# LM1117SW.net
KiCad netlist of a schematic drawn in EAGLE
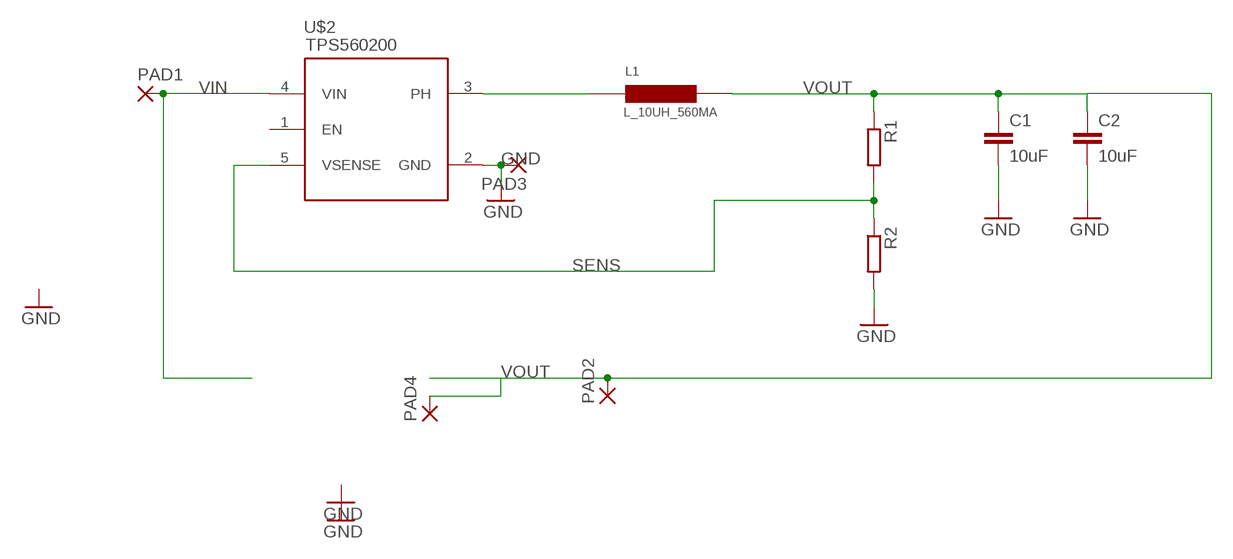
[diagram p0: schematic, sheet 1]

(export (version "E")
  (design (tool "Eeschema 10.0.6"))
  (components
    (comp (ref "C1")
      (value "10uF")
      (footprint "eagle-import:C0805K")
      (libsource (lib "eagle-import") (part "C-EUC0805K"))
    )
    (comp (ref "C2")
      (value "10uF")
      (footprint "eagle-import:C0805K")
      (libsource (lib "eagle-import") (part "C-EUC0805K"))
    )
    (comp (ref "L1")
      (value "L_10UH_560MA")
      (footprint "eagle-import:TYS3010100M-10")
      (libsource (lib "eagle-import") (part "L_10UH_560MA"))
    )
    (comp (ref "PAD1")
      (value "1,6/0,9")
      (footprint "eagle-import:1,6_0,9")
      (libsource (lib "eagle-import") (part "1,6/0,9"))
    )
    (comp (ref "PAD2")
      (value "1,6/0,9")
      (footprint "eagle-import:1,6_0,9")
      (libsource (lib "eagle-import") (part "1,6/0,9"))
    )
    (comp (ref "PAD3")
      (value "1,6/0,9")
      (footprint "eagle-import:1,6_0,9")
      (libsource (lib "eagle-import") (part "1,6/0,9"))
    )
    (comp (ref "PAD4")
      (value "1,6/0,9")
      (footprint "eagle-import:1,6_0,9")
      (libsource (lib "eagle-import") (part "1,6/0,9"))
    )
    (comp (ref "R1")
      (value "R-EU_R0402")
      (footprint "eagle-import:R0402")
      (libsource (lib "eagle-import") (part "R-EU_R0402"))
    )
    (comp (ref "R2")
      (value "R-EU_R0402")
      (footprint "eagle-import:R0402")
      (libsource (lib "eagle-import") (part "R-EU_R0402"))
    )
    (comp (ref "U$2")
      (value "TPS560200")
      (footprint "eagle-import:SOT23-5")
      (libsource (lib "eagle-import") (part "TPS560200"))
    )
  )
  (nets
    (net (code "1") (name "/SENS") (class "Default")
      (node (ref "R1") (pin "2") (pinfunction "2_2") (pintype "passive"))
      (node (ref "R2") (pin "1") (pinfunction "1_1") (pintype "passive"))
      (node (ref "U$2") (pin "5") (pinfunction "VSENSE_5") (pintype "bidirectional"))
    )
    (net (code "2") (name "/VIN") (class "Default")
      (node (ref "PAD1") (pin "1") (pinfunction "P_1") (pintype "passive"))
      (node (ref "U$2") (pin "4") (pinfunction "VIN_4") (pintype "bidirectional"))
    )
    (net (code "3") (name "/VOUT") (class "Default")
      (node (ref "C1") (pin "1") (pinfunction "1_1") (pintype "passive"))
      (node (ref "C2") (pin "1") (pinfunction "1_1") (pintype "passive"))
      (node (ref "L1") (pin "P$2") (pinfunction "P$2_P$2") (pintype "bidirectional"))
      (node (ref "PAD2") (pin "1") (pinfunction "P_1") (pintype "passive"))
      (node (ref "PAD4") (pin "1") (pinfunction "P_1") (pintype "passive"))
      (node (ref "R1") (pin "1") (pinfunction "1_1") (pintype "passive"))
    )
    (net (code "4") (name "GND") (class "Default")
      (node (ref "C1") (pin "2") (pinfunction "2_2") (pintype "passive"))
      (node (ref "C2") (pin "2") (pinfunction "2_2") (pintype "passive"))
      (node (ref "PAD3") (pin "1") (pinfunction "P_1") (pintype "passive"))
      (node (ref "R2") (pin "2") (pinfunction "2_2") (pintype "passive"))
      (node (ref "U$2") (pin "2") (pinfunction "GND_2") (pintype "bidirectional"))
    )
    (net (code "5") (name "Net-(U$2-PH)") (class "Default")
      (node (ref "L1") (pin "P$1") (pinfunction "P$1_P$1") (pintype "bidirectional"))
      (node (ref "U$2") (pin "3") (pinfunction "PH_3") (pintype "bidirectional"))
    )
    (net (code "6") (name "unconnected-(U$2-EN-Pad1)") (class "Default")
      (node (ref "U$2") (pin "1") (pinfunction "EN_1") (pintype "bidirectional"))
    )
  )
)
